# DS1307.net
KiCad netlist of a schematic drawn in Altium Designer
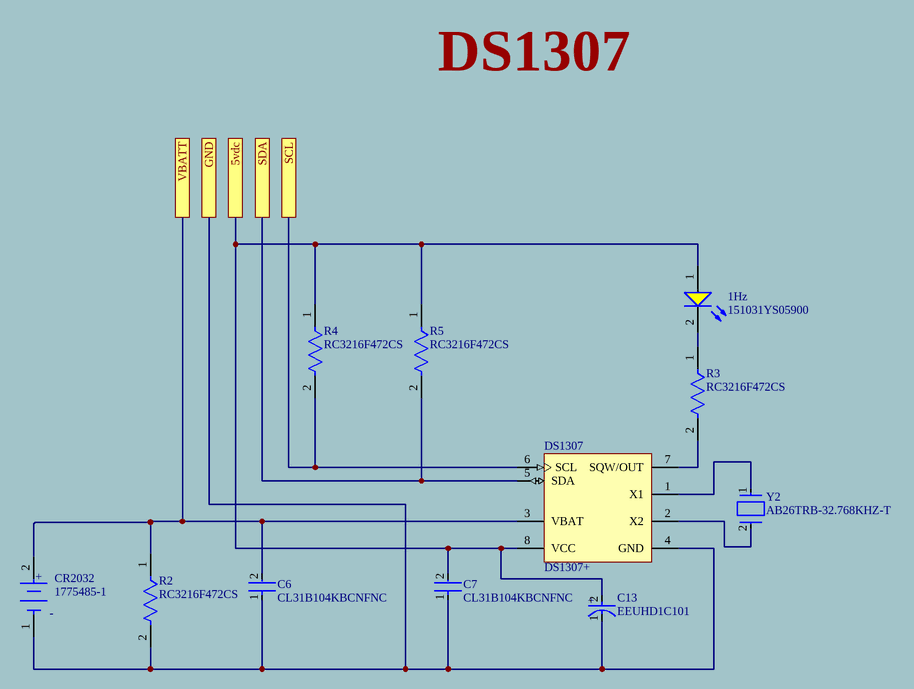
[diagram p0: DS1307.SchDoc]

(export (version "E")
  (design (tool "Eeschema 10.0.6"))
  (components
    (comp (ref "1Hz")
      (value "151031YS05900")
      (footprint "WL-TMRC_D3.95H5.3")
      (libsource (lib "Altium Content Vault") (part "LED_Yellow_1A-2K"))
    )
    (comp (ref "C6")
      (value "CL31B104KBCNFNC")
      (footprint "FP-CL31-IPC_C")
      (description "Cap Ceramic 100nF 50V X7R ±10% SMD 1206 +125°C Embossed T/R")
      (fields (field (name "TOLERANCE") "10%"))
      (libsource (lib "Altium Content Vault") (part "b4654b650e69147ec39a6b967a45e02"))
    )
    (comp (ref "C7")
      (value "CL31B104KBCNFNC")
      (footprint "FP-CL31-IPC_C")
      (description "Cap Ceramic 100nF 50V X7R ±10% SMD 1206 +125°C Embossed T/R")
      (fields (field (name "TOLERANCE") "10%"))
      (libsource (lib "Altium Content Vault") (part "b4654b650e69147ec39a6b967a45e02"))
    )
    (comp (ref "C13")
      (value "EEUHD1C101")
      (footprint "FP-RAD-TH-D_5_0_5-L_11_1-MFG")
      (description "Aluminum Electrolytic Capacitors (Radial Lead Type) AEC-Q200 Qualified 100uF ±20% 16V")
      (fields (field (name "TOLERANCE") "20%") (field (name "VOLTAGE") "16V"))
      (libsource (lib "Altium Content Vault") (part "a00bbbee19879c290e62620ae7e47b1"))
    )
    (comp (ref "CR2032")
      (value "1775485-1")
      (footprint "FP-1775485-1-MFG")
      (description "BATT HLDR COIN 20MM 1 CEL PC PIN")
      (libsource (lib "Altium Content Vault") (part "60d3b5b901a8747834971d0eb8cf3fd"))
    )
    (comp (ref "DS1307")
      (value "DS1307+")
      (footprint "P8+2")
      (description "64 x 8, Serial, I2C Real-Time Clock, 5.0V, 8-Pin PDIP, 0 to 70 degC, Pb-Free")
      (libsource (lib "Altium Content Vault") (part "PR_RTC_DS1307-IL8"))
    )
    (comp (ref "R2")
      (value "RC3216F472CS")
      (footprint "FP-RC3216-MFG")
      (description "Res Thick Film 1206 4.7kΩ 1% 0.25W ±100ppm/°C Molded SMD T/R")
      (fields (field (name "TOLERANCE") "1%"))
      (libsource (lib "Altium Content Vault") (part "1029c3af85768c4190bb7ad29bc67b5"))
    )
    (comp (ref "R3")
      (value "RC3216F472CS")
      (footprint "FP-RC3216-MFG")
      (description "Res Thick Film 1206 4.7kΩ 1% 0.25W ±100ppm/°C Molded SMD T/R")
      (fields (field (name "TOLERANCE") "1%"))
      (libsource (lib "Altium Content Vault") (part "1029c3af85768c4190bb7ad29bc67b5"))
    )
    (comp (ref "R4")
      (value "RC3216F472CS")
      (footprint "FP-RC3216-MFG")
      (description "Res Thick Film 1206 4.7kΩ 1% 0.25W ±100ppm/°C Molded SMD T/R")
      (fields (field (name "TOLERANCE") "1%"))
      (libsource (lib "Altium Content Vault") (part "1029c3af85768c4190bb7ad29bc67b5"))
    )
    (comp (ref "R5")
      (value "RC3216F472CS")
      (footprint "FP-RC3216-MFG")
      (description "Res Thick Film 1206 4.7kΩ 1% 0.25W ±100ppm/°C Molded SMD T/R")
      (fields (field (name "TOLERANCE") "1%"))
      (libsource (lib "Altium Content Vault") (part "1029c3af85768c4190bb7ad29bc67b5"))
    )
    (comp (ref "Y2")
      (value "AB26TRB-32.768KHZ-T")
      (footprint "FP-AB26TRB-MFG")
      (description "CRYSTAL 32.7680KHZ 12.5PF TH")
      (fields (field (name "TOLERANCE") "20ppm"))
      (libsource (lib "Altium Content Vault") (part "c23a69dc6c9e2f18f2079038eb95dd1"))
    )
  )
  (nets
    (net (code "1") (name "/5vdc") (class "Default")
      (node (ref "1Hz") (pin "1") (pinfunction "A_1") (pintype "passive"))
      (node (ref "C13") (pin "2") (pinfunction "A_2") (pintype "passive"))
      (node (ref "C7") (pin "2") (pinfunction "2_2") (pintype "passive"))
      (node (ref "DS1307") (pin "8") (pinfunction "VCC_8") (pintype "power_in"))
      (node (ref "R4") (pin "1") (pinfunction "1_1") (pintype "passive"))
      (node (ref "R5") (pin "1") (pinfunction "1_1") (pintype "passive"))
    )
    (net (code "2") (name "/GND") (class "Default")
      (node (ref "C13") (pin "1") (pinfunction "C_1") (pintype "passive"))
      (node (ref "C6") (pin "1") (pinfunction "1_1") (pintype "passive"))
      (node (ref "C7") (pin "1") (pinfunction "1_1") (pintype "passive"))
      (node (ref "CR2032") (pin "1") (pinfunction "C_1") (pintype "passive"))
      (node (ref "DS1307") (pin "4") (pinfunction "GND_4") (pintype "power_in"))
      (node (ref "R2") (pin "2") (pinfunction "2_2") (pintype "passive"))
    )
    (net (code "3") (name "/SCL") (class "Default")
      (node (ref "DS1307") (pin "6") (pinfunction "SCL_6") (pintype "input"))
      (node (ref "R4") (pin "2") (pinfunction "2_2") (pintype "passive"))
    )
    (net (code "4") (name "/SDA") (class "Default")
      (node (ref "DS1307") (pin "5") (pinfunction "SDA_5") (pintype "bidirectional"))
      (node (ref "R5") (pin "2") (pinfunction "2_2") (pintype "passive"))
    )
    (net (code "5") (name "/VBATT") (class "Default")
      (node (ref "C6") (pin "2") (pinfunction "2_2") (pintype "passive"))
      (node (ref "CR2032") (pin "2") (pinfunction "A_2") (pintype "passive"))
      (node (ref "DS1307") (pin "3") (pinfunction "VBAT_3") (pintype "power_in"))
      (node (ref "R2") (pin "1") (pinfunction "1_1") (pintype "passive"))
    )
    (net (code "6") (name "Net-(1Hz-K)") (class "Default")
      (node (ref "1Hz") (pin "2") (pinfunction "K_2") (pintype "passive"))
      (node (ref "R3") (pin "1") (pinfunction "1_1") (pintype "passive"))
    )
    (net (code "7") (name "Net-(DS1307-SQW{slash}OUT)") (class "Default")
      (node (ref "DS1307") (pin "7") (pinfunction "SQW/OUT_7") (pintype "open_collector"))
      (node (ref "R3") (pin "2") (pinfunction "2_2") (pintype "passive"))
    )
    (net (code "8") (name "Net-(DS1307-X1)") (class "Default")
      (node (ref "DS1307") (pin "1") (pinfunction "X1_1") (pintype "passive"))
      (node (ref "Y2") (pin "1") (pinfunction "1_1") (pintype "passive"))
    )
    (net (code "9") (name "Net-(DS1307-X2)") (class "Default")
      (node (ref "DS1307") (pin "2") (pinfunction "X2_2") (pintype "passive"))
      (node (ref "Y2") (pin "2") (pinfunction "2_2") (pintype "passive"))
    )
  )
)
